# Optical_Encoder_10-12-16.net
KiCad netlist of a schematic drawn in EAGLE
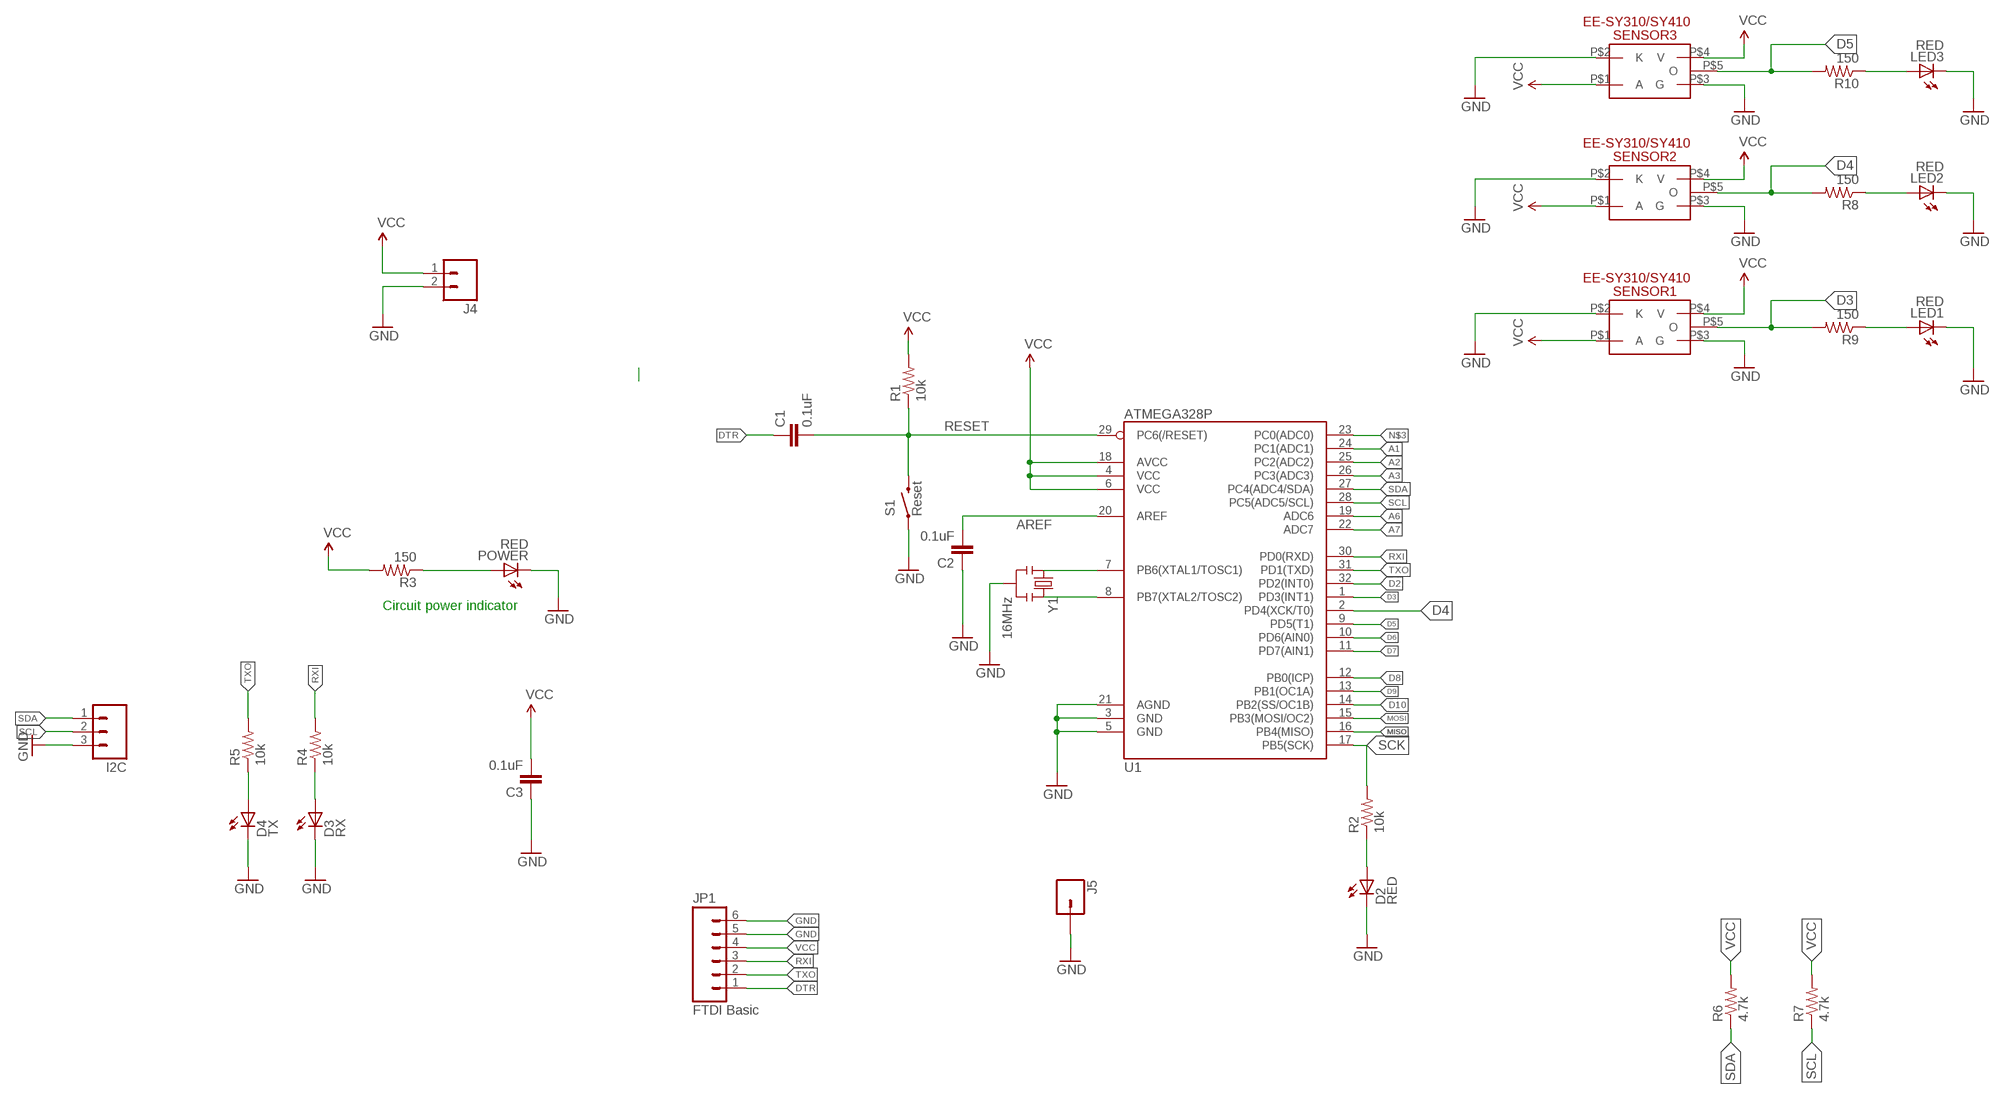
[diagram p0: schematic, sheet 1]

(export (version "E")
  (design (tool "Eeschema 10.0.6"))
  (components
    (comp (ref "C1")
      (value "0.1uF")
      (footprint "eagle-import:0603-CAP")
      (libsource (lib "eagle-import") (part "CAP0603-CAP"))
    )
    (comp (ref "C2")
      (value "0.1uF")
      (footprint "eagle-import:0603-CAP")
      (libsource (lib "eagle-import") (part "CAP0603-CAP"))
    )
    (comp (ref "C3")
      (value "0.1uF")
      (footprint "eagle-import:0603-CAP")
      (libsource (lib "eagle-import") (part "CAP0603-CAP"))
    )
    (comp (ref "D2")
      (value "RED")
      (footprint "eagle-import:LED-0603")
      (libsource (lib "eagle-import") (part "LED-RED0603"))
    )
    (comp (ref "D3")
      (value "RX")
      (footprint "eagle-import:LED-0603")
      (libsource (lib "eagle-import") (part "LED-GREEN0603"))
    )
    (comp (ref "D4")
      (value "TX")
      (footprint "eagle-import:LED-0603")
      (libsource (lib "eagle-import") (part "LED-RED0603"))
    )
    (comp (ref "I2C")
      (value "M03PTH")
      (footprint "eagle-import:1X03")
      (libsource (lib "eagle-import") (part "M03PTH"))
    )
    (comp (ref "J4")
      (value "M02PTH")
      (footprint "eagle-import:1X02")
      (libsource (lib "eagle-import") (part "M02PTH"))
    )
    (comp (ref "J5")
      (value "M01PTH")
      (footprint "eagle-import:1X01")
      (libsource (lib "eagle-import") (part "M01PTH"))
    )
    (comp (ref "JP1")
      (value "FTDI Basic")
      (footprint "eagle-import:MOLEX-1X6")
      (libsource (lib "eagle-import") (part "M06POLAR"))
    )
    (comp (ref "LED1")
      (value "RED")
      (footprint "eagle-import:LED-0603")
      (libsource (lib "eagle-import") (part "LED-RED0603"))
    )
    (comp (ref "LED2")
      (value "RED")
      (footprint "eagle-import:LED-0603")
      (libsource (lib "eagle-import") (part "LED-RED0603"))
    )
    (comp (ref "LED3")
      (value "RED")
      (footprint "eagle-import:LED-0603")
      (libsource (lib "eagle-import") (part "LED-RED0603"))
    )
    (comp (ref "POWER")
      (value "RED")
      (footprint "eagle-import:LED-0603")
      (libsource (lib "eagle-import") (part "LED-RED0603"))
    )
    (comp (ref "R1")
      (value "10k")
      (footprint "eagle-import:0603-RES")
      (libsource (lib "eagle-import") (part "RESISTOR0603-RES"))
    )
    (comp (ref "R2")
      (value "10k")
      (footprint "eagle-import:0603-RES")
      (libsource (lib "eagle-import") (part "RESISTOR0603-RES"))
    )
    (comp (ref "R3")
      (value "150")
      (footprint "eagle-import:1206")
      (libsource (lib "eagle-import") (part "SparkFun-Resistors_RESISTOR1206"))
    )
    (comp (ref "R4")
      (value "10k")
      (footprint "eagle-import:0603-RES")
      (libsource (lib "eagle-import") (part "RESISTOR0603-RES"))
    )
    (comp (ref "R5")
      (value "10k")
      (footprint "eagle-import:0603-RES")
      (libsource (lib "eagle-import") (part "RESISTOR0603-RES"))
    )
    (comp (ref "R6")
      (value "4.7k")
      (footprint "eagle-import:1206")
      (libsource (lib "eagle-import") (part "SparkFun-Resistors_RESISTOR1206"))
    )
    (comp (ref "R7")
      (value "4.7k")
      (footprint "eagle-import:1206")
      (libsource (lib "eagle-import") (part "SparkFun-Resistors_RESISTOR1206"))
    )
    (comp (ref "R8")
      (value "150")
      (footprint "eagle-import:1206")
      (libsource (lib "eagle-import") (part "SparkFun-Resistors_RESISTOR1206"))
    )
    (comp (ref "R9")
      (value "150")
      (footprint "eagle-import:1206")
      (libsource (lib "eagle-import") (part "SparkFun-Resistors_RESISTOR1206"))
    )
    (comp (ref "R10")
      (value "150")
      (footprint "eagle-import:1206")
      (libsource (lib "eagle-import") (part "SparkFun-Resistors_RESISTOR1206"))
    )
    (comp (ref "S1")
      (value "Reset")
      (footprint "eagle-import:TACTILE_SWITCH_SMD")
      (libsource (lib "eagle-import") (part "SWITCH-MOMENTARY-2SMD"))
    )
    (comp (ref "SENSOR1")
      (value "EE-SY310/SY410")
      (footprint "eagle-import:EE-SY310_SY410")
      (libsource (lib "eagle-import") (part "EE-SY310/SY410"))
    )
    (comp (ref "SENSOR2")
      (value "EE-SY310/SY410")
      (footprint "eagle-import:EE-SY310_SY410")
      (libsource (lib "eagle-import") (part "EE-SY310/SY410"))
    )
    (comp (ref "SENSOR3")
      (value "EE-SY310/SY410")
      (footprint "eagle-import:EE-SY310_SY410")
      (libsource (lib "eagle-import") (part "EE-SY310/SY410"))
    )
    (comp (ref "U1")
      (value "ATMEGA328P")
      (footprint "eagle-import:TQFP32-08")
      (libsource (lib "eagle-import") (part "ATMEGA328_SMT"))
    )
    (comp (ref "Y1")
      (value "16MHz")
      (footprint "eagle-import:RESONATOR-SMD")
      (libsource (lib "eagle-import") (part "RESONATOR16MHZ"))
    )
  )
  (nets
    (net (code "1") (name "/AREF") (class "Default")
      (node (ref "C2") (pin "2") (pinfunction "2_2") (pintype "passive"))
      (node (ref "U1") (pin "20") (pinfunction "AREF_20") (pintype "bidirectional"))
    )
    (net (code "2") (name "/RESET") (class "Default")
      (node (ref "C1") (pin "2") (pinfunction "2_2") (pintype "passive"))
      (node (ref "R1") (pin "1") (pinfunction "1_1") (pintype "passive"))
      (node (ref "S1") (pin "3") (pinfunction "2_3") (pintype "passive"))
      (node (ref "U1") (pin "29") (pinfunction "PC6(/RESET)_29") (pintype "bidirectional"))
    )
    (net (code "3") (name "A1") (class "Default")
      (node (ref "U1") (pin "24") (pinfunction "PC1(ADC1)_24") (pintype "bidirectional"))
    )
    (net (code "4") (name "A2") (class "Default")
      (node (ref "U1") (pin "25") (pinfunction "PC2(ADC2)_25") (pintype "bidirectional"))
    )
    (net (code "5") (name "A3") (class "Default")
      (node (ref "U1") (pin "26") (pinfunction "PC3(ADC3)_26") (pintype "bidirectional"))
    )
    (net (code "6") (name "A6") (class "Default")
      (node (ref "U1") (pin "19") (pinfunction "ADC6_19") (pintype "bidirectional"))
    )
    (net (code "7") (name "A7") (class "Default")
      (node (ref "U1") (pin "22") (pinfunction "ADC7_22") (pintype "bidirectional"))
    )
    (net (code "8") (name "D2") (class "Default")
      (node (ref "U1") (pin "32") (pinfunction "PD2(INT0)_32") (pintype "bidirectional"))
    )
    (net (code "9") (name "D3") (class "Default")
      (node (ref "R9") (pin "2") (pinfunction "2_2") (pintype "passive"))
      (node (ref "SENSOR1") (pin "P$5") (pinfunction "O_P$5") (pintype "bidirectional"))
      (node (ref "U1") (pin "1") (pinfunction "PD3(INT1)_1") (pintype "bidirectional"))
    )
    (net (code "10") (name "D4") (class "Default")
      (node (ref "R8") (pin "2") (pinfunction "2_2") (pintype "passive"))
      (node (ref "SENSOR2") (pin "P$5") (pinfunction "O_P$5") (pintype "bidirectional"))
      (node (ref "U1") (pin "2") (pinfunction "PD4(XCK/T0)_2") (pintype "bidirectional"))
    )
    (net (code "11") (name "D5") (class "Default")
      (node (ref "R10") (pin "2") (pinfunction "2_2") (pintype "passive"))
      (node (ref "SENSOR3") (pin "P$5") (pinfunction "O_P$5") (pintype "bidirectional"))
      (node (ref "U1") (pin "9") (pinfunction "PD5(T1)_9") (pintype "bidirectional"))
    )
    (net (code "12") (name "D6") (class "Default")
      (node (ref "U1") (pin "10") (pinfunction "PD6(AIN0)_10") (pintype "bidirectional"))
    )
    (net (code "13") (name "D7") (class "Default")
      (node (ref "U1") (pin "11") (pinfunction "PD7(AIN1)_11") (pintype "bidirectional"))
    )
    (net (code "14") (name "D8") (class "Default")
      (node (ref "U1") (pin "12") (pinfunction "PB0(ICP)_12") (pintype "bidirectional"))
    )
    (net (code "15") (name "D9") (class "Default")
      (node (ref "U1") (pin "13") (pinfunction "PB1(OC1A)_13") (pintype "bidirectional"))
    )
    (net (code "16") (name "D10") (class "Default")
      (node (ref "U1") (pin "14") (pinfunction "PB2(SS/OC1B)_14") (pintype "bidirectional"))
    )
    (net (code "17") (name "DTR") (class "Default")
      (node (ref "C1") (pin "1") (pinfunction "1_1") (pintype "passive"))
      (node (ref "JP1") (pin "1") (pinfunction "1_1") (pintype "passive"))
    )
    (net (code "18") (name "GND") (class "Default")
      (node (ref "C2") (pin "1") (pinfunction "1_1") (pintype "passive"))
      (node (ref "C3") (pin "1") (pinfunction "1_1") (pintype "passive"))
      (node (ref "D2") (pin "C") (pinfunction "C_C") (pintype "passive"))
      (node (ref "D3") (pin "C") (pinfunction "C_C") (pintype "passive"))
      (node (ref "D4") (pin "C") (pinfunction "C_C") (pintype "passive"))
      (node (ref "I2C") (pin "3") (pinfunction "3_3") (pintype "passive"))
      (node (ref "J4") (pin "2") (pinfunction "2_2") (pintype "passive"))
      (node (ref "J5") (pin "1") (pinfunction "1_1") (pintype "passive"))
      (node (ref "JP1") (pin "5") (pinfunction "5_5") (pintype "passive"))
      (node (ref "JP1") (pin "6") (pinfunction "6_6") (pintype "passive"))
      (node (ref "LED1") (pin "C") (pinfunction "C_C") (pintype "passive"))
      (node (ref "LED2") (pin "C") (pinfunction "C_C") (pintype "passive"))
      (node (ref "LED3") (pin "C") (pinfunction "C_C") (pintype "passive"))
      (node (ref "POWER") (pin "C") (pinfunction "C_C") (pintype "passive"))
      (node (ref "S1") (pin "1") (pinfunction "1_1") (pintype "passive"))
      (node (ref "SENSOR1") (pin "P$2") (pinfunction "K_P$2") (pintype "bidirectional"))
      (node (ref "SENSOR1") (pin "P$3") (pinfunction "G_P$3") (pintype "bidirectional"))
      (node (ref "SENSOR2") (pin "P$2") (pinfunction "K_P$2") (pintype "bidirectional"))
      (node (ref "SENSOR2") (pin "P$3") (pinfunction "G_P$3") (pintype "bidirectional"))
      (node (ref "SENSOR3") (pin "P$2") (pinfunction "K_P$2") (pintype "bidirectional"))
      (node (ref "SENSOR3") (pin "P$3") (pinfunction "G_P$3") (pintype "bidirectional"))
      (node (ref "U1") (pin "21") (pinfunction "AGND_21") (pintype "bidirectional"))
      (node (ref "U1") (pin "3") (pinfunction "GND_3") (pintype "bidirectional"))
      (node (ref "U1") (pin "5") (pinfunction "GND_5") (pintype "bidirectional"))
      (node (ref "Y1") (pin "2") (pinfunction "2_2") (pintype "passive"))
    )
    (net (code "19") (name "MISO") (class "Default")
      (node (ref "U1") (pin "16") (pinfunction "PB4(MISO)_16") (pintype "bidirectional"))
    )
    (net (code "20") (name "MOSI") (class "Default")
      (node (ref "U1") (pin "15") (pinfunction "PB3(MOSI/OC2)_15") (pintype "bidirectional"))
    )
    (net (code "21") (name "N$3") (class "Default")
      (node (ref "U1") (pin "23") (pinfunction "PC0(ADC0)_23") (pintype "bidirectional"))
    )
    (net (code "22") (name "Net-(D2-PadA)") (class "Default")
      (node (ref "D2") (pin "A") (pinfunction "A_A") (pintype "passive"))
      (node (ref "R2") (pin "1") (pinfunction "1_1") (pintype "passive"))
    )
    (net (code "23") (name "Net-(D3-PadA)") (class "Default")
      (node (ref "D3") (pin "A") (pinfunction "A_A") (pintype "passive"))
      (node (ref "R4") (pin "1") (pinfunction "1_1") (pintype "passive"))
    )
    (net (code "24") (name "Net-(D4-PadA)") (class "Default")
      (node (ref "D4") (pin "A") (pinfunction "A_A") (pintype "passive"))
      (node (ref "R5") (pin "1") (pinfunction "1_1") (pintype "passive"))
    )
    (net (code "25") (name "Net-(LED1-PadA)") (class "Default")
      (node (ref "LED1") (pin "A") (pinfunction "A_A") (pintype "passive"))
      (node (ref "R9") (pin "1") (pinfunction "1_1") (pintype "passive"))
    )
    (net (code "26") (name "Net-(LED2-PadA)") (class "Default")
      (node (ref "LED2") (pin "A") (pinfunction "A_A") (pintype "passive"))
      (node (ref "R8") (pin "1") (pinfunction "1_1") (pintype "passive"))
    )
    (net (code "27") (name "Net-(LED3-PadA)") (class "Default")
      (node (ref "LED3") (pin "A") (pinfunction "A_A") (pintype "passive"))
      (node (ref "R10") (pin "1") (pinfunction "1_1") (pintype "passive"))
    )
    (net (code "28") (name "Net-(POWER-PadA)") (class "Default")
      (node (ref "POWER") (pin "A") (pinfunction "A_A") (pintype "passive"))
      (node (ref "R3") (pin "1") (pinfunction "1_1") (pintype "passive"))
    )
    (net (code "29") (name "Net-(U1-PB6(XTAL1{slash}TOSC1))") (class "Default")
      (node (ref "U1") (pin "7") (pinfunction "PB6(XTAL1/TOSC1)_7") (pintype "bidirectional"))
      (node (ref "Y1") (pin "1") (pinfunction "1_1") (pintype "passive"))
    )
    (net (code "30") (name "Net-(U1-PB7(XTAL2{slash}TOSC2))") (class "Default")
      (node (ref "U1") (pin "8") (pinfunction "PB7(XTAL2/TOSC2)_8") (pintype "bidirectional"))
      (node (ref "Y1") (pin "3") (pinfunction "3_3") (pintype "passive"))
    )
    (net (code "31") (name "RXI") (class "Default")
      (node (ref "JP1") (pin "3") (pinfunction "3_3") (pintype "passive"))
      (node (ref "R4") (pin "2") (pinfunction "2_2") (pintype "passive"))
      (node (ref "U1") (pin "30") (pinfunction "PD0(RXD)_30") (pintype "bidirectional"))
    )
    (net (code "32") (name "SCK") (class "Default")
      (node (ref "R2") (pin "2") (pinfunction "2_2") (pintype "passive"))
      (node (ref "U1") (pin "17") (pinfunction "PB5(SCK)_17") (pintype "bidirectional"))
    )
    (net (code "33") (name "SCL") (class "Default")
      (node (ref "I2C") (pin "2") (pinfunction "2_2") (pintype "passive"))
      (node (ref "R7") (pin "1") (pinfunction "1_1") (pintype "passive"))
      (node (ref "U1") (pin "28") (pinfunction "PC5(ADC5/SCL)_28") (pintype "bidirectional"))
    )
    (net (code "34") (name "SDA") (class "Default")
      (node (ref "I2C") (pin "1") (pinfunction "1_1") (pintype "passive"))
      (node (ref "R6") (pin "1") (pinfunction "1_1") (pintype "passive"))
      (node (ref "U1") (pin "27") (pinfunction "PC4(ADC4/SDA)_27") (pintype "bidirectional"))
    )
    (net (code "35") (name "TXO") (class "Default")
      (node (ref "JP1") (pin "2") (pinfunction "2_2") (pintype "passive"))
      (node (ref "R5") (pin "2") (pinfunction "2_2") (pintype "passive"))
      (node (ref "U1") (pin "31") (pinfunction "PD1(TXD)_31") (pintype "bidirectional"))
    )
    (net (code "36") (name "VCC") (class "Default")
      (node (ref "C3") (pin "2") (pinfunction "2_2") (pintype "passive"))
      (node (ref "J4") (pin "1") (pinfunction "1_1") (pintype "passive"))
      (node (ref "JP1") (pin "4") (pinfunction "4_4") (pintype "passive"))
      (node (ref "R1") (pin "2") (pinfunction "2_2") (pintype "passive"))
      (node (ref "R3") (pin "2") (pinfunction "2_2") (pintype "passive"))
      (node (ref "R6") (pin "2") (pinfunction "2_2") (pintype "passive"))
      (node (ref "R7") (pin "2") (pinfunction "2_2") (pintype "passive"))
      (node (ref "SENSOR1") (pin "P$1") (pinfunction "A_P$1") (pintype "bidirectional"))
      (node (ref "SENSOR1") (pin "P$4") (pinfunction "V_P$4") (pintype "bidirectional"))
      (node (ref "SENSOR2") (pin "P$1") (pinfunction "A_P$1") (pintype "bidirectional"))
      (node (ref "SENSOR2") (pin "P$4") (pinfunction "V_P$4") (pintype "bidirectional"))
      (node (ref "SENSOR3") (pin "P$1") (pinfunction "A_P$1") (pintype "bidirectional"))
      (node (ref "SENSOR3") (pin "P$4") (pinfunction "V_P$4") (pintype "bidirectional"))
      (node (ref "U1") (pin "18") (pinfunction "AVCC_18") (pintype "bidirectional"))
      (node (ref "U1") (pin "4") (pinfunction "VCC_4") (pintype "bidirectional"))
      (node (ref "U1") (pin "6") (pinfunction "VCC_6") (pintype "bidirectional"))
    )
  )
)
